# Voltage_Measurement.net
KiCad netlist of a schematic drawn in Altium Designer
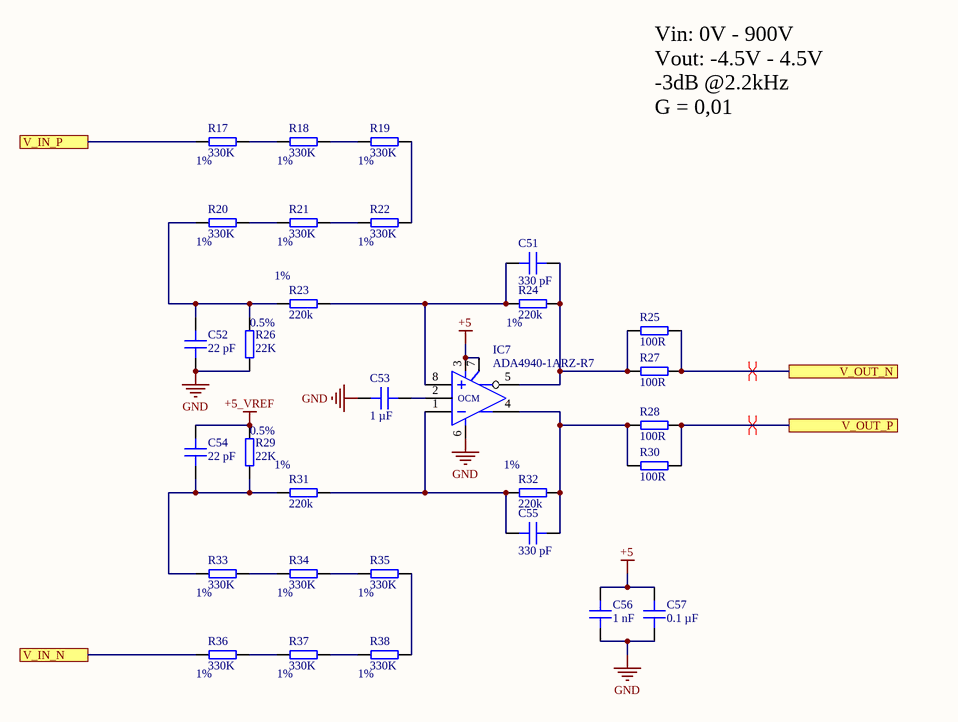
[diagram p0: Voltage_Measurement.SchDoc]

(export (version "E")
  (design (tool "Eeschema 10.0.6"))
  (components
    (comp (ref "C51")
      (value "330 pF")
      (footprint "C_0603")
      (description "Capacitor 0603, 50 VDC, 330 pF, X7R")
      (fields
        (field (name "MANUFACTURER PART NUMBER") "C0603X331J5RAC3112")
        (field (name "MANUFACTURER") "KEMET")
        (field (name "CREATED FROM") "MGremer")
      )
      (libsource (lib "user") (part "Capacitor"))
    )
    (comp (ref "C52")
      (value "22 pF")
      (footprint "C_0603")
      (description "Capacitor 0603, 50 VDC, 22 pF, X7R")
      (fields
        (field (name "MANUFACTURER PART NUMBER") "C0603C220J5RACTU")
        (field (name "MANUFACTURER") "KEMET")
        (field (name "CREATED FROM") "MGremer")
      )
      (libsource (lib "user") (part "Capacitor"))
    )
    (comp (ref "C53")
      (value "1 µF")
      (footprint "C_0603")
      (description "50V 1uF X7R ±10% 0603 Multilayer Ceramic Capacitors MLCC - SMD/SMT ROHS")
      (fields
        (field (name "MANUFACTURER PART NUMBER") "UMK107AB7105KA-T")
        (field (name "MANUFACTURER") "Taiyo Yuden")
        (field (name "CREATED FROM") "NDiringer")
      )
      (libsource (lib "user") (part "Capacitor"))
    )
    (comp (ref "C54")
      (value "22 pF")
      (footprint "C_0603")
      (description "Capacitor 0603, 50 VDC, 22 pF, X7R")
      (fields
        (field (name "MANUFACTURER PART NUMBER") "C0603C220J5RACTU")
        (field (name "MANUFACTURER") "KEMET")
        (field (name "CREATED FROM") "MGremer")
      )
      (libsource (lib "user") (part "Capacitor"))
    )
    (comp (ref "C55")
      (value "330 pF")
      (footprint "C_0603")
      (description "Capacitor 0603, 50 VDC, 330 pF, X7R")
      (fields
        (field (name "MANUFACTURER PART NUMBER") "C0603X331J5RAC3112")
        (field (name "MANUFACTURER") "KEMET")
        (field (name "CREATED FROM") "MGremer")
      )
      (libsource (lib "user") (part "Capacitor"))
    )
    (comp (ref "C56")
      (value "1 nF")
      (footprint "C_0603")
      (description "Capacitor 0603, 50 VDC, 1 nF, NP0")
      (fields
        (field (name "MANUFACTURER PART NUMBER") "CC0603JRNPO9BN102")
        (field (name "MANUFACTURER") "YAGEO")
        (field (name "CREATED FROM") "AGeiger")
      )
      (libsource (lib "user") (part "Capacitor"))
    )
    (comp (ref "C57")
      (value "0.1 µF")
      (footprint "C_0603")
      (description "Capacitor 0603, 50 VDC, 0.1 µF, X7R")
      (fields
        (field (name "MANUFACTURER PART NUMBER") "C0603X104K5RAC7411")
        (field (name "MANUFACTURER") "KEMET")
        (field (name "CREATED FROM") "MGremer")
      )
      (libsource (lib "user") (part "Capacitor"))
    )
    (comp (ref "IC7")
      (value "ADA4940-1ARZ-R7")
      (footprint "SOIC-8-N")
      (description "Differential ADC Driver")
      (fields (field (name "MANUFACTURER") "Analog Devices") (field (name "CREATED FROM") "MGremer"))
      (libsource (lib "user") (part "ADA4940-1ARZ"))
    )
    (comp (ref "R17")
      (value "330K")
      (footprint "RES 1206_3216")
      (description "SMD resistor E24 series 330K OHM 1% 50PPM 1/4W")
      (fields
        (field (name "MANUFACTURER PART NUMBER") "RT1206FRE07330KL")
        (field (name "MANUFACTURER") "YAGEO")
        (field (name "TOLERANCE") "1%")
        (field (name "CREATED FROM") "StarostV")
      )
      (libsource (lib "user") (part "Resistor"))
    )
    (comp (ref "R18")
      (value "330K")
      (footprint "RES 1206_3216")
      (description "SMD resistor E24 series 330K OHM 1% 50PPM 1/4W")
      (fields
        (field (name "MANUFACTURER PART NUMBER") "RT1206FRE07330KL")
        (field (name "MANUFACTURER") "YAGEO")
        (field (name "TOLERANCE") "1%")
        (field (name "CREATED FROM") "StarostV")
      )
      (libsource (lib "user") (part "Resistor"))
    )
    (comp (ref "R19")
      (value "330K")
      (footprint "RES 1206_3216")
      (description "SMD resistor E24 series 330K OHM 1% 50PPM 1/4W")
      (fields
        (field (name "MANUFACTURER PART NUMBER") "RT1206FRE07330KL")
        (field (name "MANUFACTURER") "YAGEO")
        (field (name "TOLERANCE") "1%")
        (field (name "CREATED FROM") "StarostV")
      )
      (libsource (lib "user") (part "Resistor"))
    )
    (comp (ref "R20")
      (value "330K")
      (footprint "RES 1206_3216")
      (description "SMD resistor E24 series 330K OHM 1% 50PPM 1/4W")
      (fields
        (field (name "MANUFACTURER PART NUMBER") "RT1206FRE07330KL")
        (field (name "MANUFACTURER") "YAGEO")
        (field (name "TOLERANCE") "1%")
        (field (name "CREATED FROM") "StarostV")
      )
      (libsource (lib "user") (part "Resistor"))
    )
    (comp (ref "R21")
      (value "330K")
      (footprint "RES 1206_3216")
      (description "SMD resistor E24 series 330K OHM 1% 50PPM 1/4W")
      (fields
        (field (name "MANUFACTURER PART NUMBER") "RT1206FRE07330KL")
        (field (name "MANUFACTURER") "YAGEO")
        (field (name "TOLERANCE") "1%")
        (field (name "CREATED FROM") "StarostV")
      )
      (libsource (lib "user") (part "Resistor"))
    )
    (comp (ref "R22")
      (value "330K")
      (footprint "RES 1206_3216")
      (description "SMD resistor E24 series 330K OHM 1% 50PPM 1/4W")
      (fields
        (field (name "MANUFACTURER PART NUMBER") "RT1206FRE07330KL")
        (field (name "MANUFACTURER") "YAGEO")
        (field (name "TOLERANCE") "1%")
        (field (name "CREATED FROM") "StarostV")
      )
      (libsource (lib "user") (part "Resistor"))
    )
    (comp (ref "R23")
      (value "220k")
      (footprint "RES 0603_1608")
      (description "SMD resistor 1%")
      (fields
        (field (name "MANUFACTURER PART NUMBER") "AC0603FR-07220KL")
        (field (name "MANUFACTURER") "YAGEO")
        (field (name "TOLERANCE") "1%")
        (field (name "CREATED FROM") "VStarost")
      )
      (libsource (lib "user") (part "Resistor"))
    )
    (comp (ref "R24")
      (value "220k")
      (footprint "RES 0603_1608")
      (description "SMD resistor 1%")
      (fields
        (field (name "MANUFACTURER PART NUMBER") "AC0603FR-07220KL")
        (field (name "MANUFACTURER") "YAGEO")
        (field (name "TOLERANCE") "1%")
        (field (name "CREATED FROM") "VStarost")
      )
      (libsource (lib "user") (part "Resistor"))
    )
    (comp (ref "R25")
      (value "100R")
      (footprint "RES 0603_1608")
      (description "SMD resistor E24 series")
      (fields
        (field (name "MANUFACTURER PART NUMBER") "RK73B1JTTD101J")
        (field (name "MANUFACTURER") "KOA Speer")
        (field (name "CREATED FROM") "MGremer")
      )
      (libsource (lib "user") (part "Resistor"))
    )
    (comp (ref "R26")
      (value "22K")
      (footprint "RES 0603_1608")
      (description "SMD resistor E24 series 22K 0.5% 1/10W 75 Volts 50ppm")
      (fields
        (field (name "MANUFACTURER PART NUMBER") "RT0603DRE0722KL")
        (field (name "MANUFACTURER") "YAGEO")
        (field (name "TOLERANCE") "0.5%")
        (field (name "CREATED FROM") "VStarost")
      )
      (libsource (lib "user") (part "Resistor"))
    )
    (comp (ref "R27")
      (value "100R")
      (footprint "RES 0603_1608")
      (description "SMD resistor E24 series")
      (fields
        (field (name "MANUFACTURER PART NUMBER") "RK73B1JTTD101J")
        (field (name "MANUFACTURER") "KOA Speer")
        (field (name "CREATED FROM") "MGremer")
      )
      (libsource (lib "user") (part "Resistor"))
    )
    (comp (ref "R28")
      (value "100R")
      (footprint "RES 0603_1608")
      (description "SMD resistor E24 series")
      (fields
        (field (name "MANUFACTURER PART NUMBER") "RK73B1JTTD101J")
        (field (name "MANUFACTURER") "KOA Speer")
        (field (name "CREATED FROM") "MGremer")
      )
      (libsource (lib "user") (part "Resistor"))
    )
    (comp (ref "R29")
      (value "22K")
      (footprint "RES 0603_1608")
      (description "SMD resistor E24 series 22K 0.5% 1/10W 75 Volts 50ppm")
      (fields
        (field (name "MANUFACTURER PART NUMBER") "RT0603DRE0722KL")
        (field (name "MANUFACTURER") "YAGEO")
        (field (name "TOLERANCE") "0.5%")
        (field (name "CREATED FROM") "VStarost")
      )
      (libsource (lib "user") (part "Resistor"))
    )
    (comp (ref "R30")
      (value "100R")
      (footprint "RES 0603_1608")
      (description "SMD resistor E24 series")
      (fields
        (field (name "MANUFACTURER PART NUMBER") "RK73B1JTTD101J")
        (field (name "MANUFACTURER") "KOA Speer")
        (field (name "CREATED FROM") "MGremer")
      )
      (libsource (lib "user") (part "Resistor"))
    )
    (comp (ref "R31")
      (value "220k")
      (footprint "RES 0603_1608")
      (description "SMD resistor 1%")
      (fields
        (field (name "MANUFACTURER PART NUMBER") "AC0603FR-07220KL")
        (field (name "MANUFACTURER") "YAGEO")
        (field (name "TOLERANCE") "1%")
        (field (name "CREATED FROM") "VStarost")
      )
      (libsource (lib "user") (part "Resistor"))
    )
    (comp (ref "R32")
      (value "220k")
      (footprint "RES 0603_1608")
      (description "SMD resistor 1%")
      (fields
        (field (name "MANUFACTURER PART NUMBER") "AC0603FR-07220KL")
        (field (name "MANUFACTURER") "YAGEO")
        (field (name "TOLERANCE") "1%")
        (field (name "CREATED FROM") "VStarost")
      )
      (libsource (lib "user") (part "Resistor"))
    )
    (comp (ref "R33")
      (value "330K")
      (footprint "RES 1206_3216")
      (description "SMD resistor E24 series 330K OHM 1% 50PPM 1/4W")
      (fields
        (field (name "MANUFACTURER PART NUMBER") "RT1206FRE07330KL")
        (field (name "MANUFACTURER") "YAGEO")
        (field (name "TOLERANCE") "1%")
        (field (name "CREATED FROM") "StarostV")
      )
      (libsource (lib "user") (part "Resistor"))
    )
    (comp (ref "R34")
      (value "330K")
      (footprint "RES 1206_3216")
      (description "SMD resistor E24 series 330K OHM 1% 50PPM 1/4W")
      (fields
        (field (name "MANUFACTURER PART NUMBER") "RT1206FRE07330KL")
        (field (name "MANUFACTURER") "YAGEO")
        (field (name "TOLERANCE") "1%")
        (field (name "CREATED FROM") "StarostV")
      )
      (libsource (lib "user") (part "Resistor"))
    )
    (comp (ref "R35")
      (value "330K")
      (footprint "RES 1206_3216")
      (description "SMD resistor E24 series 330K OHM 1% 50PPM 1/4W")
      (fields
        (field (name "MANUFACTURER PART NUMBER") "RT1206FRE07330KL")
        (field (name "MANUFACTURER") "YAGEO")
        (field (name "TOLERANCE") "1%")
        (field (name "CREATED FROM") "StarostV")
      )
      (libsource (lib "user") (part "Resistor"))
    )
    (comp (ref "R36")
      (value "330K")
      (footprint "RES 1206_3216")
      (description "SMD resistor E24 series 330K OHM 1% 50PPM 1/4W")
      (fields
        (field (name "MANUFACTURER PART NUMBER") "RT1206FRE07330KL")
        (field (name "MANUFACTURER") "YAGEO")
        (field (name "TOLERANCE") "1%")
        (field (name "CREATED FROM") "StarostV")
      )
      (libsource (lib "user") (part "Resistor"))
    )
    (comp (ref "R37")
      (value "330K")
      (footprint "RES 1206_3216")
      (description "SMD resistor E24 series 330K OHM 1% 50PPM 1/4W")
      (fields
        (field (name "MANUFACTURER PART NUMBER") "RT1206FRE07330KL")
        (field (name "MANUFACTURER") "YAGEO")
        (field (name "TOLERANCE") "1%")
        (field (name "CREATED FROM") "StarostV")
      )
      (libsource (lib "user") (part "Resistor"))
    )
    (comp (ref "R38")
      (value "330K")
      (footprint "RES 1206_3216")
      (description "SMD resistor E24 series 330K OHM 1% 50PPM 1/4W")
      (fields
        (field (name "MANUFACTURER PART NUMBER") "RT1206FRE07330KL")
        (field (name "MANUFACTURER") "YAGEO")
        (field (name "TOLERANCE") "1%")
        (field (name "CREATED FROM") "StarostV")
      )
      (libsource (lib "user") (part "Resistor"))
    )
  )
  (nets
    (net (code "1") (name "+5") (class "Default")
      (node (ref "C56") (pin "2") (pinfunction "2_2") (pintype "passive"))
      (node (ref "C57") (pin "2") (pinfunction "2_2") (pintype "passive"))
      (node (ref "IC7") (pin "3") (pinfunction "V+_3") (pintype "passive"))
      (node (ref "IC7") (pin "7") (pinfunction "EN_7") (pintype "passive"))
    )
    (net (code "2") (name "+5_VREF") (class "Default")
      (node (ref "C54") (pin "2") (pinfunction "2_2") (pintype "passive"))
      (node (ref "R29") (pin "2") (pinfunction "2_2") (pintype "passive"))
    )
    (net (code "3") (name "/V_IN_N") (class "Default")
      (node (ref "R36") (pin "1") (pinfunction "1_1") (pintype "passive"))
    )
    (net (code "4") (name "/V_IN_P") (class "Default")
      (node (ref "R17") (pin "1") (pinfunction "1_1") (pintype "passive"))
    )
    (net (code "5") (name "/V_OUT_N") (class "Default")
      (node (ref "R25") (pin "2") (pinfunction "2_2") (pintype "passive"))
      (node (ref "R27") (pin "2") (pinfunction "2_2") (pintype "passive"))
    )
    (net (code "6") (name "/V_OUT_P") (class "Default")
      (node (ref "R28") (pin "2") (pinfunction "2_2") (pintype "passive"))
      (node (ref "R30") (pin "2") (pinfunction "2_2") (pintype "passive"))
    )
    (net (code "7") (name "GND") (class "Default")
      (node (ref "C52") (pin "1") (pinfunction "1_1") (pintype "passive"))
      (node (ref "C53") (pin "1") (pinfunction "1_1") (pintype "passive"))
      (node (ref "C56") (pin "1") (pinfunction "1_1") (pintype "passive"))
      (node (ref "C57") (pin "1") (pinfunction "1_1") (pintype "passive"))
      (node (ref "IC7") (pin "6") (pinfunction "V-_6") (pintype "passive"))
      (node (ref "R26") (pin "1") (pinfunction "1_1") (pintype "passive"))
    )
    (net (code "8") (name "Net-(C51-Pad2)") (class "Default")
      (node (ref "C51") (pin "2") (pinfunction "2_2") (pintype "passive"))
      (node (ref "IC7") (pin "5") (pinfunction "Out_5") (pintype "passive"))
      (node (ref "R24") (pin "2") (pinfunction "2_2") (pintype "passive"))
      (node (ref "R25") (pin "1") (pinfunction "1_1") (pintype "passive"))
      (node (ref "R27") (pin "1") (pinfunction "1_1") (pintype "passive"))
    )
    (net (code "9") (name "Net-(C52-Pad2)") (class "Default")
      (node (ref "C52") (pin "2") (pinfunction "2_2") (pintype "passive"))
      (node (ref "R20") (pin "1") (pinfunction "1_1") (pintype "passive"))
      (node (ref "R23") (pin "1") (pinfunction "1_1") (pintype "passive"))
      (node (ref "R26") (pin "2") (pinfunction "2_2") (pintype "passive"))
    )
    (net (code "10") (name "Net-(C54-Pad1)") (class "Default")
      (node (ref "C54") (pin "1") (pinfunction "1_1") (pintype "passive"))
      (node (ref "R29") (pin "1") (pinfunction "1_1") (pintype "passive"))
      (node (ref "R31") (pin "1") (pinfunction "1_1") (pintype "passive"))
      (node (ref "R33") (pin "1") (pinfunction "1_1") (pintype "passive"))
    )
    (net (code "11") (name "Net-(C55-Pad2)") (class "Default")
      (node (ref "C55") (pin "2") (pinfunction "2_2") (pintype "passive"))
      (node (ref "IC7") (pin "4") (pinfunction "Out_4") (pintype "passive"))
      (node (ref "R28") (pin "1") (pinfunction "1_1") (pintype "passive"))
      (node (ref "R30") (pin "1") (pinfunction "1_1") (pintype "passive"))
      (node (ref "R32") (pin "2") (pinfunction "2_2") (pintype "passive"))
    )
    (net (code "12") (name "Net-(IC7-+)") (class "Default")
      (node (ref "C51") (pin "1") (pinfunction "1_1") (pintype "passive"))
      (node (ref "IC7") (pin "8") (pinfunction "+_8") (pintype "passive"))
      (node (ref "R23") (pin "2") (pinfunction "2_2") (pintype "passive"))
      (node (ref "R24") (pin "1") (pinfunction "1_1") (pintype "passive"))
    )
    (net (code "13") (name "Net-(IC7--)") (class "Default")
      (node (ref "C55") (pin "1") (pinfunction "1_1") (pintype "passive"))
      (node (ref "IC7") (pin "1") (pinfunction "-_1") (pintype "passive"))
      (node (ref "R31") (pin "2") (pinfunction "2_2") (pintype "passive"))
      (node (ref "R32") (pin "1") (pinfunction "1_1") (pintype "passive"))
    )
    (net (code "14") (name "Net-(IC7-OCM)") (class "Default")
      (node (ref "C53") (pin "2") (pinfunction "2_2") (pintype "passive"))
      (node (ref "IC7") (pin "2") (pinfunction "OCM_2") (pintype "passive"))
    )
    (net (code "15") (name "Net-(R17-Pad2)") (class "Default")
      (node (ref "R17") (pin "2") (pinfunction "2_2") (pintype "passive"))
      (node (ref "R18") (pin "1") (pinfunction "1_1") (pintype "passive"))
    )
    (net (code "16") (name "Net-(R18-Pad2)") (class "Default")
      (node (ref "R18") (pin "2") (pinfunction "2_2") (pintype "passive"))
      (node (ref "R19") (pin "1") (pinfunction "1_1") (pintype "passive"))
    )
    (net (code "17") (name "Net-(R19-Pad2)") (class "Default")
      (node (ref "R19") (pin "2") (pinfunction "2_2") (pintype "passive"))
      (node (ref "R22") (pin "2") (pinfunction "2_2") (pintype "passive"))
    )
    (net (code "18") (name "Net-(R20-Pad2)") (class "Default")
      (node (ref "R20") (pin "2") (pinfunction "2_2") (pintype "passive"))
      (node (ref "R21") (pin "1") (pinfunction "1_1") (pintype "passive"))
    )
    (net (code "19") (name "Net-(R21-Pad2)") (class "Default")
      (node (ref "R21") (pin "2") (pinfunction "2_2") (pintype "passive"))
      (node (ref "R22") (pin "1") (pinfunction "1_1") (pintype "passive"))
    )
    (net (code "20") (name "Net-(R33-Pad2)") (class "Default")
      (node (ref "R33") (pin "2") (pinfunction "2_2") (pintype "passive"))
      (node (ref "R34") (pin "1") (pinfunction "1_1") (pintype "passive"))
    )
    (net (code "21") (name "Net-(R34-Pad2)") (class "Default")
      (node (ref "R34") (pin "2") (pinfunction "2_2") (pintype "passive"))
      (node (ref "R35") (pin "1") (pinfunction "1_1") (pintype "passive"))
    )
    (net (code "22") (name "Net-(R35-Pad2)") (class "Default")
      (node (ref "R35") (pin "2") (pinfunction "2_2") (pintype "passive"))
      (node (ref "R38") (pin "2") (pinfunction "2_2") (pintype "passive"))
    )
    (net (code "23") (name "Net-(R36-Pad2)") (class "Default")
      (node (ref "R36") (pin "2") (pinfunction "2_2") (pintype "passive"))
      (node (ref "R37") (pin "1") (pinfunction "1_1") (pintype "passive"))
    )
    (net (code "24") (name "Net-(R37-Pad2)") (class "Default")
      (node (ref "R37") (pin "2") (pinfunction "2_2") (pintype "passive"))
      (node (ref "R38") (pin "1") (pinfunction "1_1") (pintype "passive"))
    )
  )
)
